# releborne.net
KiCad netlist of a schematic drawn in EAGLE
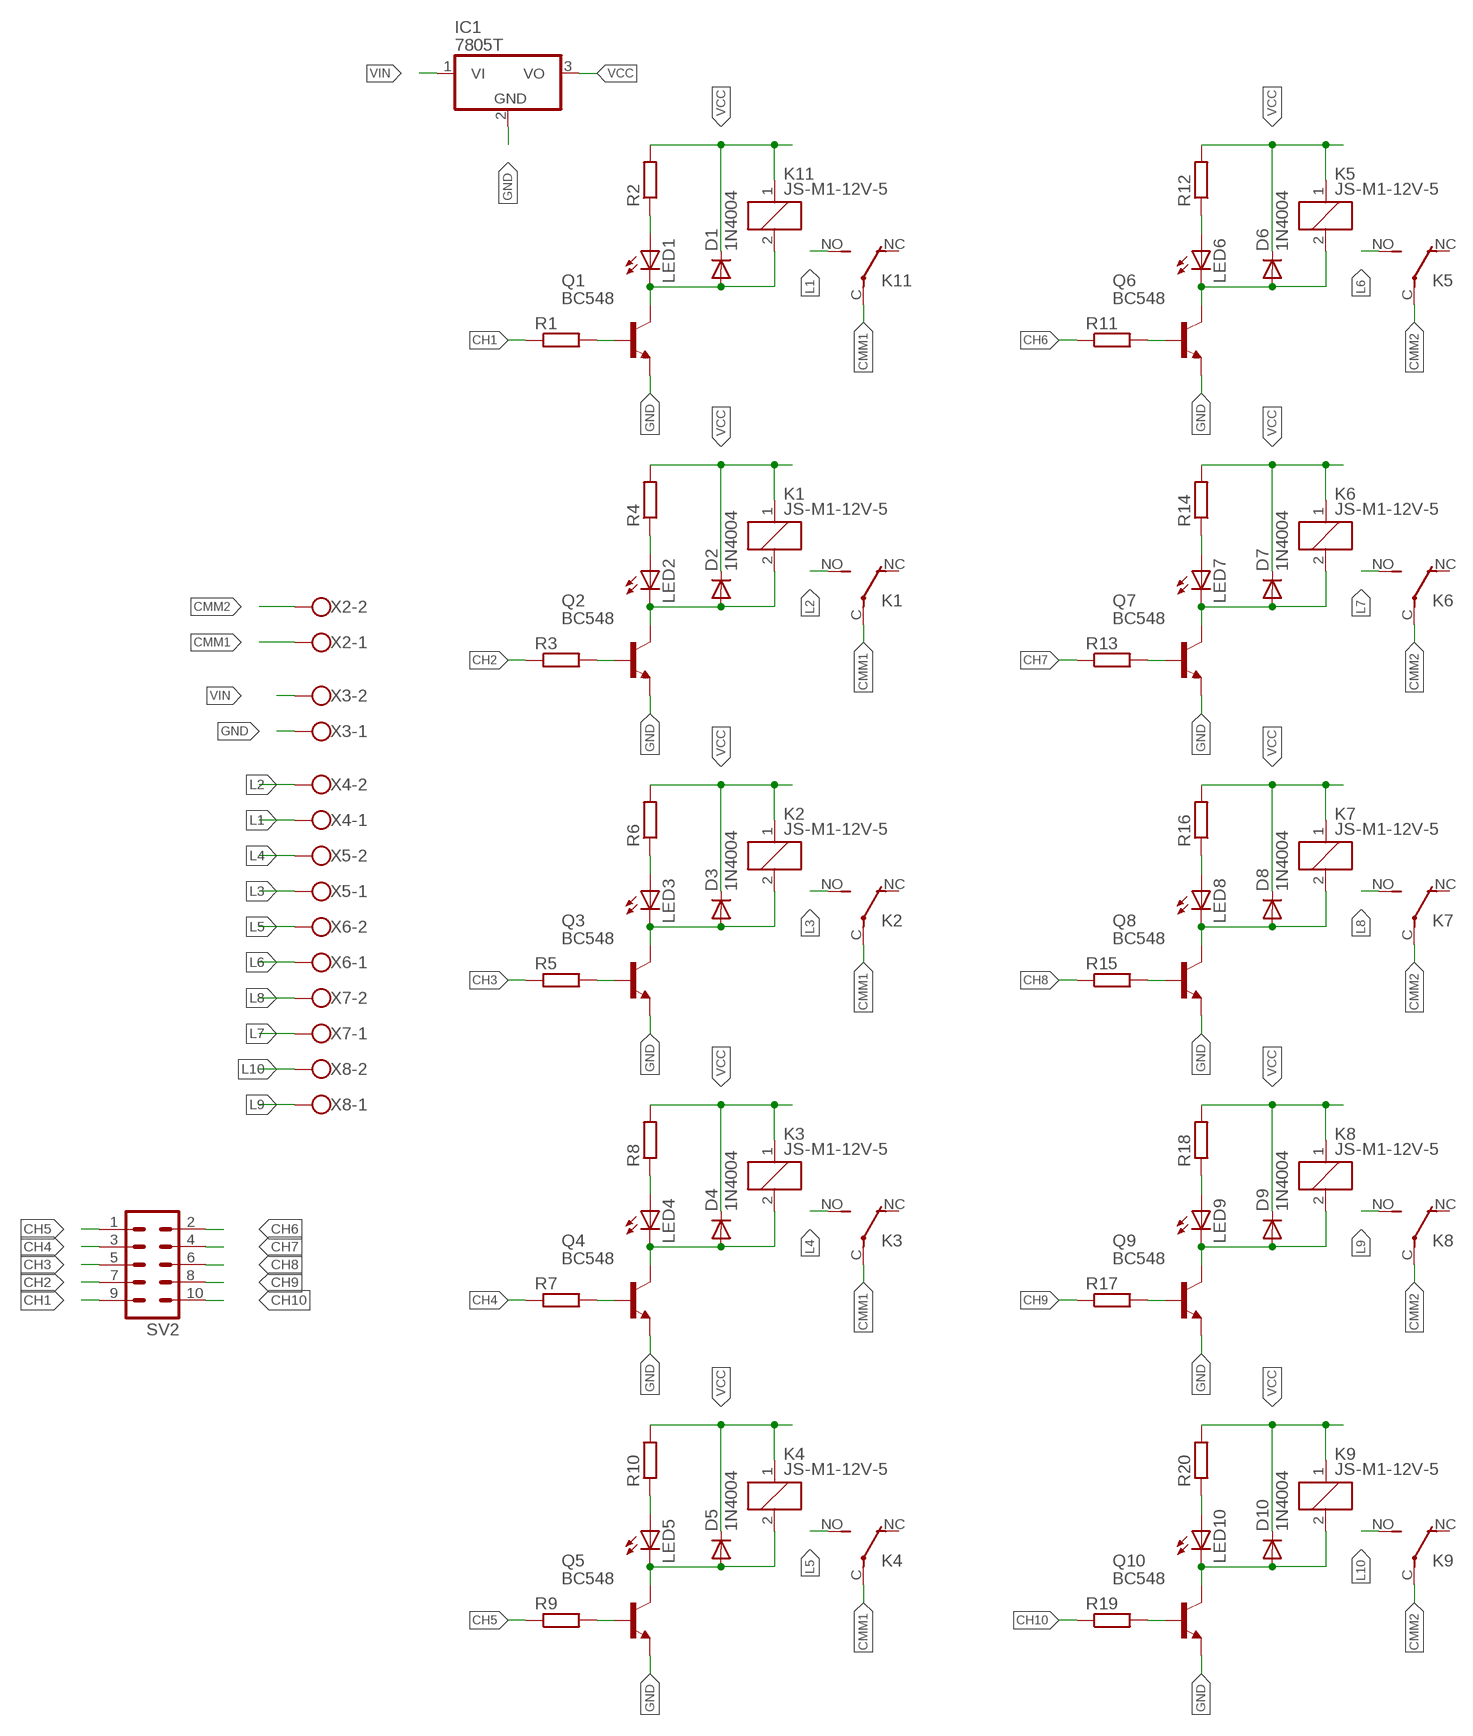
[diagram p0: schematic, sheet 1]

(export (version "E")
  (design (tool "Eeschema 10.0.6"))
  (components
    (comp (ref "D1")
      (value "1N4004")
      (footprint "eagle-import:DO41-10")
      (libsource (lib "eagle-import") (part "1N4004"))
    )
    (comp (ref "D2")
      (value "1N4004")
      (footprint "eagle-import:DO41-10")
      (libsource (lib "eagle-import") (part "1N4004"))
    )
    (comp (ref "D3")
      (value "1N4004")
      (footprint "eagle-import:DO41-10")
      (libsource (lib "eagle-import") (part "1N4004"))
    )
    (comp (ref "D4")
      (value "1N4004")
      (footprint "eagle-import:DO41-10")
      (libsource (lib "eagle-import") (part "1N4004"))
    )
    (comp (ref "D5")
      (value "1N4004")
      (footprint "eagle-import:DO41-10")
      (libsource (lib "eagle-import") (part "1N4004"))
    )
    (comp (ref "D6")
      (value "1N4004")
      (footprint "eagle-import:DO41-10")
      (libsource (lib "eagle-import") (part "1N4004"))
    )
    (comp (ref "D7")
      (value "1N4004")
      (footprint "eagle-import:DO41-10")
      (libsource (lib "eagle-import") (part "1N4004"))
    )
    (comp (ref "D8")
      (value "1N4004")
      (footprint "eagle-import:DO41-10")
      (libsource (lib "eagle-import") (part "1N4004"))
    )
    (comp (ref "D9")
      (value "1N4004")
      (footprint "eagle-import:DO41-10")
      (libsource (lib "eagle-import") (part "1N4004"))
    )
    (comp (ref "D10")
      (value "1N4004")
      (footprint "eagle-import:DO41-10")
      (libsource (lib "eagle-import") (part "1N4004"))
    )
    (comp (ref "IC1")
      (value "7805T")
      (footprint "eagle-import:TO220H")
      (libsource (lib "eagle-import") (part "78T05"))
    )
    (comp (ref "K1")
      (value "JS-M1-12V-5")
      (footprint "eagle-import:JS-M")
      (fields (field (name "MF") "FARNELL") (field (name "MPN") "JSM1-12V-5"))
      (libsource (lib "eagle-import") (part "JS-M1-12V-5"))
    )
    (comp (ref "K2")
      (value "JS-M1-12V-5")
      (footprint "eagle-import:JS-M")
      (fields (field (name "MF") "FARNELL") (field (name "MPN") "JSM1-12V-5"))
      (libsource (lib "eagle-import") (part "JS-M1-12V-5"))
    )
    (comp (ref "K3")
      (value "JS-M1-12V-5")
      (footprint "eagle-import:JS-M")
      (fields (field (name "MF") "FARNELL") (field (name "MPN") "JSM1-12V-5"))
      (libsource (lib "eagle-import") (part "JS-M1-12V-5"))
    )
    (comp (ref "K4")
      (value "JS-M1-12V-5")
      (footprint "eagle-import:JS-M")
      (fields (field (name "MF") "FARNELL") (field (name "MPN") "JSM1-12V-5"))
      (libsource (lib "eagle-import") (part "JS-M1-12V-5"))
    )
    (comp (ref "K5")
      (value "JS-M1-12V-5")
      (footprint "eagle-import:JS-M")
      (fields (field (name "MF") "FARNELL") (field (name "MPN") "JSM1-12V-5"))
      (libsource (lib "eagle-import") (part "JS-M1-12V-5"))
    )
    (comp (ref "K6")
      (value "JS-M1-12V-5")
      (footprint "eagle-import:JS-M")
      (fields (field (name "MF") "FARNELL") (field (name "MPN") "JSM1-12V-5"))
      (libsource (lib "eagle-import") (part "JS-M1-12V-5"))
    )
    (comp (ref "K7")
      (value "JS-M1-12V-5")
      (footprint "eagle-import:JS-M")
      (fields (field (name "MF") "FARNELL") (field (name "MPN") "JSM1-12V-5"))
      (libsource (lib "eagle-import") (part "JS-M1-12V-5"))
    )
    (comp (ref "K8")
      (value "JS-M1-12V-5")
      (footprint "eagle-import:JS-M")
      (fields (field (name "MF") "FARNELL") (field (name "MPN") "JSM1-12V-5"))
      (libsource (lib "eagle-import") (part "JS-M1-12V-5"))
    )
    (comp (ref "K9")
      (value "JS-M1-12V-5")
      (footprint "eagle-import:JS-M")
      (fields (field (name "MF") "FARNELL") (field (name "MPN") "JSM1-12V-5"))
      (libsource (lib "eagle-import") (part "JS-M1-12V-5"))
    )
    (comp (ref "K11")
      (value "JS-M1-12V-5")
      (footprint "eagle-import:JS-M")
      (fields (field (name "MF") "FARNELL") (field (name "MPN") "JSM1-12V-5"))
      (libsource (lib "eagle-import") (part "JS-M1-12V-5"))
    )
    (comp (ref "LED1")
      (value "LED5MM")
      (footprint "eagle-import:LED5MM")
      (libsource (lib "eagle-import") (part "LED5MM"))
    )
    (comp (ref "LED2")
      (value "LED5MM")
      (footprint "eagle-import:LED5MM")
      (libsource (lib "eagle-import") (part "LED5MM"))
    )
    (comp (ref "LED3")
      (value "LED5MM")
      (footprint "eagle-import:LED5MM")
      (libsource (lib "eagle-import") (part "LED5MM"))
    )
    (comp (ref "LED4")
      (value "LED5MM")
      (footprint "eagle-import:LED5MM")
      (libsource (lib "eagle-import") (part "LED5MM"))
    )
    (comp (ref "LED5")
      (value "LED5MM")
      (footprint "eagle-import:LED5MM")
      (libsource (lib "eagle-import") (part "LED5MM"))
    )
    (comp (ref "LED6")
      (value "LED5MM")
      (footprint "eagle-import:LED5MM")
      (libsource (lib "eagle-import") (part "LED5MM"))
    )
    (comp (ref "LED7")
      (value "LED5MM")
      (footprint "eagle-import:LED5MM")
      (libsource (lib "eagle-import") (part "LED5MM"))
    )
    (comp (ref "LED8")
      (value "LED5MM")
      (footprint "eagle-import:LED5MM")
      (libsource (lib "eagle-import") (part "LED5MM"))
    )
    (comp (ref "LED9")
      (value "LED5MM")
      (footprint "eagle-import:LED5MM")
      (libsource (lib "eagle-import") (part "LED5MM"))
    )
    (comp (ref "LED10")
      (value "LED5MM")
      (footprint "eagle-import:LED5MM")
      (libsource (lib "eagle-import") (part "LED5MM"))
    )
    (comp (ref "Q1")
      (value "BC548")
      (footprint "eagle-import:TO92-EBC")
      (libsource (lib "eagle-import") (part "BC548"))
    )
    (comp (ref "Q2")
      (value "BC548")
      (footprint "eagle-import:TO92-EBC")
      (libsource (lib "eagle-import") (part "BC548"))
    )
    (comp (ref "Q3")
      (value "BC548")
      (footprint "eagle-import:TO92-EBC")
      (libsource (lib "eagle-import") (part "BC548"))
    )
    (comp (ref "Q4")
      (value "BC548")
      (footprint "eagle-import:TO92-EBC")
      (libsource (lib "eagle-import") (part "BC548"))
    )
    (comp (ref "Q5")
      (value "BC548")
      (footprint "eagle-import:TO92-EBC")
      (libsource (lib "eagle-import") (part "BC548"))
    )
    (comp (ref "Q6")
      (value "BC548")
      (footprint "eagle-import:TO92-EBC")
      (libsource (lib "eagle-import") (part "BC548"))
    )
    (comp (ref "Q7")
      (value "BC548")
      (footprint "eagle-import:TO92-EBC")
      (libsource (lib "eagle-import") (part "BC548"))
    )
    (comp (ref "Q8")
      (value "BC548")
      (footprint "eagle-import:TO92-EBC")
      (libsource (lib "eagle-import") (part "BC548"))
    )
    (comp (ref "Q9")
      (value "BC548")
      (footprint "eagle-import:TO92-EBC")
      (libsource (lib "eagle-import") (part "BC548"))
    )
    (comp (ref "Q10")
      (value "BC548")
      (footprint "eagle-import:TO92-EBC")
      (libsource (lib "eagle-import") (part "BC548"))
    )
    (comp (ref "R1")
      (value "R-EU_0207/10")
      (footprint "eagle-import:0207_10")
      (libsource (lib "eagle-import") (part "R-EU_0207/10"))
    )
    (comp (ref "R2")
      (value "R-EU_0207/10")
      (footprint "eagle-import:0207_10")
      (libsource (lib "eagle-import") (part "R-EU_0207/10"))
    )
    (comp (ref "R3")
      (value "R-EU_0207/10")
      (footprint "eagle-import:0207_10")
      (libsource (lib "eagle-import") (part "R-EU_0207/10"))
    )
    (comp (ref "R4")
      (value "R-EU_0207/10")
      (footprint "eagle-import:0207_10")
      (libsource (lib "eagle-import") (part "R-EU_0207/10"))
    )
    (comp (ref "R5")
      (value "R-EU_0207/10")
      (footprint "eagle-import:0207_10")
      (libsource (lib "eagle-import") (part "R-EU_0207/10"))
    )
    (comp (ref "R6")
      (value "R-EU_0207/10")
      (footprint "eagle-import:0207_10")
      (libsource (lib "eagle-import") (part "R-EU_0207/10"))
    )
    (comp (ref "R7")
      (value "R-EU_0207/10")
      (footprint "eagle-import:0207_10")
      (libsource (lib "eagle-import") (part "R-EU_0207/10"))
    )
    (comp (ref "R8")
      (value "R-EU_0207/10")
      (footprint "eagle-import:0207_10")
      (libsource (lib "eagle-import") (part "R-EU_0207/10"))
    )
    (comp (ref "R9")
      (value "R-EU_0207/10")
      (footprint "eagle-import:0207_10")
      (libsource (lib "eagle-import") (part "R-EU_0207/10"))
    )
    (comp (ref "R10")
      (value "R-EU_0207/10")
      (footprint "eagle-import:0207_10")
      (libsource (lib "eagle-import") (part "R-EU_0207/10"))
    )
    (comp (ref "R11")
      (value "R-EU_0207/10")
      (footprint "eagle-import:0207_10")
      (libsource (lib "eagle-import") (part "R-EU_0207/10"))
    )
    (comp (ref "R12")
      (value "R-EU_0207/10")
      (footprint "eagle-import:0207_10")
      (libsource (lib "eagle-import") (part "R-EU_0207/10"))
    )
    (comp (ref "R13")
      (value "R-EU_0207/10")
      (footprint "eagle-import:0207_10")
      (libsource (lib "eagle-import") (part "R-EU_0207/10"))
    )
    (comp (ref "R14")
      (value "R-EU_0207/10")
      (footprint "eagle-import:0207_10")
      (libsource (lib "eagle-import") (part "R-EU_0207/10"))
    )
    (comp (ref "R15")
      (value "R-EU_0207/10")
      (footprint "eagle-import:0207_10")
      (libsource (lib "eagle-import") (part "R-EU_0207/10"))
    )
    (comp (ref "R16")
      (value "R-EU_0207/10")
      (footprint "eagle-import:0207_10")
      (libsource (lib "eagle-import") (part "R-EU_0207/10"))
    )
    (comp (ref "R17")
      (value "R-EU_0207/10")
      (footprint "eagle-import:0207_10")
      (libsource (lib "eagle-import") (part "R-EU_0207/10"))
    )
    (comp (ref "R18")
      (value "R-EU_0207/10")
      (footprint "eagle-import:0207_10")
      (libsource (lib "eagle-import") (part "R-EU_0207/10"))
    )
    (comp (ref "R19")
      (value "R-EU_0207/10")
      (footprint "eagle-import:0207_10")
      (libsource (lib "eagle-import") (part "R-EU_0207/10"))
    )
    (comp (ref "R20")
      (value "R-EU_0207/10")
      (footprint "eagle-import:0207_10")
      (libsource (lib "eagle-import") (part "R-EU_0207/10"))
    )
    (comp (ref "SV2")
      (value "MA05-2")
      (footprint "eagle-import:MA05-2")
      (libsource (lib "eagle-import") (part "MA05-2"))
    )
    (comp (ref "X2")
      (value "W237-102")
      (footprint "eagle-import:W237-102")
      (fields (field (name "MPN") "237-102"))
      (libsource (lib "eagle-import") (part "W237-102"))
    )
    (comp (ref "X3")
      (value "W237-102")
      (footprint "eagle-import:W237-102")
      (fields (field (name "MPN") "237-102"))
      (libsource (lib "eagle-import") (part "W237-102"))
    )
    (comp (ref "X4")
      (value "W237-102")
      (footprint "eagle-import:W237-102")
      (fields (field (name "MPN") "237-102"))
      (libsource (lib "eagle-import") (part "W237-102"))
    )
    (comp (ref "X5")
      (value "W237-102")
      (footprint "eagle-import:W237-102")
      (fields (field (name "MPN") "237-102"))
      (libsource (lib "eagle-import") (part "W237-102"))
    )
    (comp (ref "X6")
      (value "W237-102")
      (footprint "eagle-import:W237-102")
      (fields (field (name "MPN") "237-102"))
      (libsource (lib "eagle-import") (part "W237-102"))
    )
    (comp (ref "X7")
      (value "W237-102")
      (footprint "eagle-import:W237-102")
      (fields (field (name "MPN") "237-102"))
      (libsource (lib "eagle-import") (part "W237-102"))
    )
    (comp (ref "X8")
      (value "W237-102")
      (footprint "eagle-import:W237-102")
      (fields (field (name "MPN") "237-102"))
      (libsource (lib "eagle-import") (part "W237-102"))
    )
  )
  (nets
    (net (code "1") (name "CH1") (class "Default")
      (node (ref "R1") (pin "1") (pinfunction "1_1") (pintype "passive"))
      (node (ref "SV2") (pin "9") (pinfunction "9_9") (pintype "passive"))
    )
    (net (code "2") (name "CH2") (class "Default")
      (node (ref "R3") (pin "1") (pinfunction "1_1") (pintype "passive"))
      (node (ref "SV2") (pin "7") (pinfunction "7_7") (pintype "passive"))
    )
    (net (code "3") (name "CH3") (class "Default")
      (node (ref "R5") (pin "1") (pinfunction "1_1") (pintype "passive"))
      (node (ref "SV2") (pin "5") (pinfunction "5_5") (pintype "passive"))
    )
    (net (code "4") (name "CH4") (class "Default")
      (node (ref "R7") (pin "1") (pinfunction "1_1") (pintype "passive"))
      (node (ref "SV2") (pin "3") (pinfunction "3_3") (pintype "passive"))
    )
    (net (code "5") (name "CH5") (class "Default")
      (node (ref "R9") (pin "1") (pinfunction "1_1") (pintype "passive"))
      (node (ref "SV2") (pin "1") (pinfunction "1_1") (pintype "passive"))
    )
    (net (code "6") (name "CH6") (class "Default")
      (node (ref "R11") (pin "1") (pinfunction "1_1") (pintype "passive"))
      (node (ref "SV2") (pin "2") (pinfunction "2_2") (pintype "passive"))
    )
    (net (code "7") (name "CH7") (class "Default")
      (node (ref "R13") (pin "1") (pinfunction "1_1") (pintype "passive"))
      (node (ref "SV2") (pin "4") (pinfunction "4_4") (pintype "passive"))
    )
    (net (code "8") (name "CH8") (class "Default")
      (node (ref "R15") (pin "1") (pinfunction "1_1") (pintype "passive"))
      (node (ref "SV2") (pin "6") (pinfunction "6_6") (pintype "passive"))
    )
    (net (code "9") (name "CH9") (class "Default")
      (node (ref "R17") (pin "1") (pinfunction "1_1") (pintype "passive"))
      (node (ref "SV2") (pin "8") (pinfunction "8_8") (pintype "passive"))
    )
    (net (code "10") (name "CH10") (class "Default")
      (node (ref "R19") (pin "1") (pinfunction "1_1") (pintype "passive"))
      (node (ref "SV2") (pin "10") (pinfunction "10_10") (pintype "passive"))
    )
    (net (code "11") (name "CMM1") (class "Default")
      (node (ref "K1") (pin "C") (pinfunction "P_C") (pintype "passive"))
      (node (ref "K11") (pin "C") (pinfunction "P_C") (pintype "passive"))
      (node (ref "K2") (pin "C") (pinfunction "P_C") (pintype "passive"))
      (node (ref "K3") (pin "C") (pinfunction "P_C") (pintype "passive"))
      (node (ref "K4") (pin "C") (pinfunction "P_C") (pintype "passive"))
      (node (ref "X2") (pin "1") (pinfunction "KL_1") (pintype "passive"))
    )
    (net (code "12") (name "CMM2") (class "Default")
      (node (ref "K5") (pin "C") (pinfunction "P_C") (pintype "passive"))
      (node (ref "K6") (pin "C") (pinfunction "P_C") (pintype "passive"))
      (node (ref "K7") (pin "C") (pinfunction "P_C") (pintype "passive"))
      (node (ref "K8") (pin "C") (pinfunction "P_C") (pintype "passive"))
      (node (ref "K9") (pin "C") (pinfunction "P_C") (pintype "passive"))
      (node (ref "X2") (pin "2") (pinfunction "KL_2") (pintype "passive"))
    )
    (net (code "13") (name "GND") (class "Default")
      (node (ref "IC1") (pin "2") (pinfunction "GND_2") (pintype "passive"))
      (node (ref "Q1") (pin "E") (pinfunction "E_E") (pintype "passive"))
      (node (ref "Q10") (pin "E") (pinfunction "E_E") (pintype "passive"))
      (node (ref "Q2") (pin "E") (pinfunction "E_E") (pintype "passive"))
      (node (ref "Q3") (pin "E") (pinfunction "E_E") (pintype "passive"))
      (node (ref "Q4") (pin "E") (pinfunction "E_E") (pintype "passive"))
      (node (ref "Q5") (pin "E") (pinfunction "E_E") (pintype "passive"))
      (node (ref "Q6") (pin "E") (pinfunction "E_E") (pintype "passive"))
      (node (ref "Q7") (pin "E") (pinfunction "E_E") (pintype "passive"))
      (node (ref "Q8") (pin "E") (pinfunction "E_E") (pintype "passive"))
      (node (ref "Q9") (pin "E") (pinfunction "E_E") (pintype "passive"))
      (node (ref "X3") (pin "1") (pinfunction "KL_1") (pintype "passive"))
    )
    (net (code "14") (name "L1") (class "Default")
      (node (ref "K11") (pin "NO") (pinfunction "S_NO") (pintype "passive"))
      (node (ref "X4") (pin "1") (pinfunction "KL_1") (pintype "passive"))
    )
    (net (code "15") (name "L2") (class "Default")
      (node (ref "K1") (pin "NO") (pinfunction "S_NO") (pintype "passive"))
      (node (ref "X4") (pin "2") (pinfunction "KL_2") (pintype "passive"))
    )
    (net (code "16") (name "L3") (class "Default")
      (node (ref "K2") (pin "NO") (pinfunction "S_NO") (pintype "passive"))
      (node (ref "X5") (pin "1") (pinfunction "KL_1") (pintype "passive"))
    )
    (net (code "17") (name "L4") (class "Default")
      (node (ref "K3") (pin "NO") (pinfunction "S_NO") (pintype "passive"))
      (node (ref "X5") (pin "2") (pinfunction "KL_2") (pintype "passive"))
    )
    (net (code "18") (name "L5") (class "Default")
      (node (ref "K4") (pin "NO") (pinfunction "S_NO") (pintype "passive"))
      (node (ref "X6") (pin "2") (pinfunction "KL_2") (pintype "passive"))
    )
    (net (code "19") (name "L6") (class "Default")
      (node (ref "K5") (pin "NO") (pinfunction "S_NO") (pintype "passive"))
      (node (ref "X6") (pin "1") (pinfunction "KL_1") (pintype "passive"))
    )
    (net (code "20") (name "L7") (class "Default")
      (node (ref "K6") (pin "NO") (pinfunction "S_NO") (pintype "passive"))
      (node (ref "X7") (pin "1") (pinfunction "KL_1") (pintype "passive"))
    )
    (net (code "21") (name "L8") (class "Default")
      (node (ref "K7") (pin "NO") (pinfunction "S_NO") (pintype "passive"))
      (node (ref "X7") (pin "2") (pinfunction "KL_2") (pintype "passive"))
    )
    (net (code "22") (name "L9") (class "Default")
      (node (ref "K8") (pin "NO") (pinfunction "S_NO") (pintype "passive"))
      (node (ref "X8") (pin "1") (pinfunction "KL_1") (pintype "passive"))
    )
    (net (code "23") (name "L10") (class "Default")
      (node (ref "K9") (pin "NO") (pinfunction "S_NO") (pintype "passive"))
      (node (ref "X8") (pin "2") (pinfunction "KL_2") (pintype "passive"))
    )
    (net (code "24") (name "Net-(LED1-C)") (class "Default")
      (node (ref "D1") (pin "A") (pinfunction "A_A") (pintype "passive"))
      (node (ref "K11") (pin "2") (pinfunction "2_2") (pintype "passive"))
      (node (ref "LED1") (pin "K") (pinfunction "C_K") (pintype "passive"))
      (node (ref "Q1") (pin "C") (pinfunction "C_C") (pintype "passive"))
    )
    (net (code "25") (name "Net-(LED1-PadA)") (class "Default")
      (node (ref "LED1") (pin "A") (pinfunction "A_A") (pintype "passive"))
      (node (ref "R2") (pin "1") (pinfunction "1_1") (pintype "passive"))
    )
    (net (code "26") (name "Net-(LED2-C)") (class "Default")
      (node (ref "D2") (pin "A") (pinfunction "A_A") (pintype "passive"))
      (node (ref "K1") (pin "2") (pinfunction "2_2") (pintype "passive"))
      (node (ref "LED2") (pin "K") (pinfunction "C_K") (pintype "passive"))
      (node (ref "Q2") (pin "C") (pinfunction "C_C") (pintype "passive"))
    )
    (net (code "27") (name "Net-(LED2-PadA)") (class "Default")
      (node (ref "LED2") (pin "A") (pinfunction "A_A") (pintype "passive"))
      (node (ref "R4") (pin "1") (pinfunction "1_1") (pintype "passive"))
    )
    (net (code "28") (name "Net-(LED3-C)") (class "Default")
      (node (ref "D3") (pin "A") (pinfunction "A_A") (pintype "passive"))
      (node (ref "K2") (pin "2") (pinfunction "2_2") (pintype "passive"))
      (node (ref "LED3") (pin "K") (pinfunction "C_K") (pintype "passive"))
      (node (ref "Q3") (pin "C") (pinfunction "C_C") (pintype "passive"))
    )
    (net (code "29") (name "Net-(LED3-PadA)") (class "Default")
      (node (ref "LED3") (pin "A") (pinfunction "A_A") (pintype "passive"))
      (node (ref "R6") (pin "1") (pinfunction "1_1") (pintype "passive"))
    )
    (net (code "30") (name "Net-(LED4-C)") (class "Default")
      (node (ref "D4") (pin "A") (pinfunction "A_A") (pintype "passive"))
      (node (ref "K3") (pin "2") (pinfunction "2_2") (pintype "passive"))
      (node (ref "LED4") (pin "K") (pinfunction "C_K") (pintype "passive"))
      (node (ref "Q4") (pin "C") (pinfunction "C_C") (pintype "passive"))
    )
    (net (code "31") (name "Net-(LED4-PadA)") (class "Default")
      (node (ref "LED4") (pin "A") (pinfunction "A_A") (pintype "passive"))
      (node (ref "R8") (pin "1") (pinfunction "1_1") (pintype "passive"))
    )
    (net (code "32") (name "Net-(LED5-C)") (class "Default")
      (node (ref "D5") (pin "A") (pinfunction "A_A") (pintype "passive"))
      (node (ref "K4") (pin "2") (pinfunction "2_2") (pintype "passive"))
      (node (ref "LED5") (pin "K") (pinfunction "C_K") (pintype "passive"))
      (node (ref "Q5") (pin "C") (pinfunction "C_C") (pintype "passive"))
    )
    (net (code "33") (name "Net-(LED5-PadA)") (class "Default")
      (node (ref "LED5") (pin "A") (pinfunction "A_A") (pintype "passive"))
      (node (ref "R10") (pin "1") (pinfunction "1_1") (pintype "passive"))
    )
    (net (code "34") (name "Net-(LED6-C)") (class "Default")
      (node (ref "D6") (pin "A") (pinfunction "A_A") (pintype "passive"))
      (node (ref "K5") (pin "2") (pinfunction "2_2") (pintype "passive"))
      (node (ref "LED6") (pin "K") (pinfunction "C_K") (pintype "passive"))
      (node (ref "Q6") (pin "C") (pinfunction "C_C") (pintype "passive"))
    )
    (net (code "35") (name "Net-(LED6-PadA)") (class "Default")
      (node (ref "LED6") (pin "A") (pinfunction "A_A") (pintype "passive"))
      (node (ref "R12") (pin "1") (pinfunction "1_1") (pintype "passive"))
    )
    (net (code "36") (name "Net-(LED7-C)") (class "Default")
      (node (ref "D7") (pin "A") (pinfunction "A_A") (pintype "passive"))
      (node (ref "K6") (pin "2") (pinfunction "2_2") (pintype "passive"))
      (node (ref "LED7") (pin "K") (pinfunction "C_K") (pintype "passive"))
      (node (ref "Q7") (pin "C") (pinfunction "C_C") (pintype "passive"))
    )
    (net (code "37") (name "Net-(LED7-PadA)") (class "Default")
      (node (ref "LED7") (pin "A") (pinfunction "A_A") (pintype "passive"))
      (node (ref "R14") (pin "1") (pinfunction "1_1") (pintype "passive"))
    )
    (net (code "38") (name "Net-(LED8-C)") (class "Default")
      (node (ref "D8") (pin "A") (pinfunction "A_A") (pintype "passive"))
      (node (ref "K7") (pin "2") (pinfunction "2_2") (pintype "passive"))
      (node (ref "LED8") (pin "K") (pinfunction "C_K") (pintype "passive"))
      (node (ref "Q8") (pin "C") (pinfunction "C_C") (pintype "passive"))
    )
    (net (code "39") (name "Net-(LED8-PadA)") (class "Default")
      (node (ref "LED8") (pin "A") (pinfunction "A_A") (pintype "passive"))
      (node (ref "R16") (pin "1") (pinfunction "1_1") (pintype "passive"))
    )
    (net (code "40") (name "Net-(LED9-C)") (class "Default")
      (node (ref "D9") (pin "A") (pinfunction "A_A") (pintype "passive"))
      (node (ref "K8") (pin "2") (pinfunction "2_2") (pintype "passive"))
      (node (ref "LED9") (pin "K") (pinfunction "C_K") (pintype "passive"))
      (node (ref "Q9") (pin "C") (pinfunction "C_C") (pintype "passive"))
    )
    (net (code "41") (name "Net-(LED9-PadA)") (class "Default")
      (node (ref "LED9") (pin "A") (pinfunction "A_A") (pintype "passive"))
      (node (ref "R18") (pin "1") (pinfunction "1_1") (pintype "passive"))
    )
    (net (code "42") (name "Net-(LED10-C)") (class "Default")
      (node (ref "D10") (pin "A") (pinfunction "A_A") (pintype "passive"))
      (node (ref "K9") (pin "2") (pinfunction "2_2") (pintype "passive"))
      (node (ref "LED10") (pin "K") (pinfunction "C_K") (pintype "passive"))
      (node (ref "Q10") (pin "C") (pinfunction "C_C") (pintype "passive"))
    )
    (net (code "43") (name "Net-(LED10-PadA)") (class "Default")
      (node (ref "LED10") (pin "A") (pinfunction "A_A") (pintype "passive"))
      (node (ref "R20") (pin "1") (pinfunction "1_1") (pintype "passive"))
    )
    (net (code "44") (name "Net-(Q1-PadB)") (class "Default")
      (node (ref "Q1") (pin "B") (pinfunction "B_B") (pintype "passive"))
      (node (ref "R1") (pin "2") (pinfunction "2_2") (pintype "passive"))
    )
    (net (code "45") (name "Net-(Q2-PadB)") (class "Default")
      (node (ref "Q2") (pin "B") (pinfunction "B_B") (pintype "passive"))
      (node (ref "R3") (pin "2") (pinfunction "2_2") (pintype "passive"))
    )
    (net (code "46") (name "Net-(Q3-PadB)") (class "Default")
      (node (ref "Q3") (pin "B") (pinfunction "B_B") (pintype "passive"))
      (node (ref "R5") (pin "2") (pinfunction "2_2") (pintype "passive"))
    )
    (net (code "47") (name "Net-(Q4-PadB)") (class "Default")
      (node (ref "Q4") (pin "B") (pinfunction "B_B") (pintype "passive"))
      (node (ref "R7") (pin "2") (pinfunction "2_2") (pintype "passive"))
    )
    (net (code "48") (name "Net-(Q5-PadB)") (class "Default")
      (node (ref "Q5") (pin "B") (pinfunction "B_B") (pintype "passive"))
      (node (ref "R9") (pin "2") (pinfunction "2_2") (pintype "passive"))
    )
    (net (code "49") (name "Net-(Q6-PadB)") (class "Default")
      (node (ref "Q6") (pin "B") (pinfunction "B_B") (pintype "passive"))
      (node (ref "R11") (pin "2") (pinfunction "2_2") (pintype "passive"))
    )
    (net (code "50") (name "Net-(Q7-PadB)") (class "Default")
      (node (ref "Q7") (pin "B") (pinfunction "B_B") (pintype "passive"))
      (node (ref "R13") (pin "2") (pinfunction "2_2") (pintype "passive"))
    )
    (net (code "51") (name "Net-(Q8-PadB)") (class "Default")
      (node (ref "Q8") (pin "B") (pinfunction "B_B") (pintype "passive"))
      (node (ref "R15") (pin "2") (pinfunction "2_2") (pintype "passive"))
    )
    (net (code "52") (name "Net-(Q9-PadB)") (class "Default")
      (node (ref "Q9") (pin "B") (pinfunction "B_B") (pintype "passive"))
      (node (ref "R17") (pin "2") (pinfunction "2_2") (pintype "passive"))
    )
    (net (code "53") (name "Net-(Q10-PadB)") (class "Default")
      (node (ref "Q10") (pin "B") (pinfunction "B_B") (pintype "passive"))
      (node (ref "R19") (pin "2") (pinfunction "2_2") (pintype "passive"))
    )
    (net (code "54") (name "VCC") (class "Default")
      (node (ref "D1") (pin "C") (pinfunction "C_C") (pintype "passive"))
      (node (ref "D10") (pin "C") (pinfunction "C_C") (pintype "passive"))
      (node (ref "D2") (pin "C") (pinfunction "C_C") (pintype "passive"))
      (node (ref "D3") (pin "C") (pinfunction "C_C") (pintype "passive"))
      (node (ref "D4") (pin "C") (pinfunction "C_C") (pintype "passive"))
      (node (ref "D5") (pin "C") (pinfunction "C_C") (pintype "passive"))
      (node (ref "D6") (pin "C") (pinfunction "C_C") (pintype "passive"))
      (node (ref "D7") (pin "C") (pinfunction "C_C") (pintype "passive"))
      (node (ref "D8") (pin "C") (pinfunction "C_C") (pintype "passive"))
      (node (ref "D9") (pin "C") (pinfunction "C_C") (pintype "passive"))
      (node (ref "IC1") (pin "3") (pinfunction "VO_3") (pintype "passive"))
      (node (ref "K1") (pin "1") (pinfunction "1_1") (pintype "passive"))
      (node (ref "K11") (pin "1") (pinfunction "1_1") (pintype "passive"))
      (node (ref "K2") (pin "1") (pinfunction "1_1") (pintype "passive"))
      (node (ref "K3") (pin "1") (pinfunction "1_1") (pintype "passive"))
      (node (ref "K4") (pin "1") (pinfunction "1_1") (pintype "passive"))
      (node (ref "K5") (pin "1") (pinfunction "1_1") (pintype "passive"))
      (node (ref "K6") (pin "1") (pinfunction "1_1") (pintype "passive"))
      (node (ref "K7") (pin "1") (pinfunction "1_1") (pintype "passive"))
      (node (ref "K8") (pin "1") (pinfunction "1_1") (pintype "passive"))
      (node (ref "K9") (pin "1") (pinfunction "1_1") (pintype "passive"))
      (node (ref "R10") (pin "2") (pinfunction "2_2") (pintype "passive"))
      (node (ref "R12") (pin "2") (pinfunction "2_2") (pintype "passive"))
      (node (ref "R14") (pin "2") (pinfunction "2_2") (pintype "passive"))
      (node (ref "R16") (pin "2") (pinfunction "2_2") (pintype "passive"))
      (node (ref "R18") (pin "2") (pinfunction "2_2") (pintype "passive"))
      (node (ref "R2") (pin "2") (pinfunction "2_2") (pintype "passive"))
      (node (ref "R20") (pin "2") (pinfunction "2_2") (pintype "passive"))
      (node (ref "R4") (pin "2") (pinfunction "2_2") (pintype "passive"))
      (node (ref "R6") (pin "2") (pinfunction "2_2") (pintype "passive"))
      (node (ref "R8") (pin "2") (pinfunction "2_2") (pintype "passive"))
    )
    (net (code "55") (name "VIN") (class "Default")
      (node (ref "IC1") (pin "1") (pinfunction "VI_1") (pintype "input"))
      (node (ref "X3") (pin "2") (pinfunction "KL_2") (pintype "passive"))
    )
    (net (code "56") (name "unconnected-(K1B-O-PadNC)") (class "Default")
      (node (ref "K1") (pin "NC") (pinfunction "O_NC") (pintype "passive"))
    )
    (net (code "57") (name "unconnected-(K2B-O-PadNC)") (class "Default")
      (node (ref "K2") (pin "NC") (pinfunction "O_NC") (pintype "passive"))
    )
    (net (code "58") (name "unconnected-(K3B-O-PadNC)") (class "Default")
      (node (ref "K3") (pin "NC") (pinfunction "O_NC") (pintype "passive"))
    )
    (net (code "59") (name "unconnected-(K4B-O-PadNC)") (class "Default")
      (node (ref "K4") (pin "NC") (pinfunction "O_NC") (pintype "passive"))
    )
    (net (code "60") (name "unconnected-(K5B-O-PadNC)") (class "Default")
      (node (ref "K5") (pin "NC") (pinfunction "O_NC") (pintype "passive"))
    )
    (net (code "61") (name "unconnected-(K6B-O-PadNC)") (class "Default")
      (node (ref "K6") (pin "NC") (pinfunction "O_NC") (pintype "passive"))
    )
    (net (code "62") (name "unconnected-(K7B-O-PadNC)") (class "Default")
      (node (ref "K7") (pin "NC") (pinfunction "O_NC") (pintype "passive"))
    )
    (net (code "63") (name "unconnected-(K8B-O-PadNC)") (class "Default")
      (node (ref "K8") (pin "NC") (pinfunction "O_NC") (pintype "passive"))
    )
    (net (code "64") (name "unconnected-(K9B-O-PadNC)") (class "Default")
      (node (ref "K9") (pin "NC") (pinfunction "O_NC") (pintype "passive"))
    )
    (net (code "65") (name "unconnected-(K11B-O-PadNC)") (class "Default")
      (node (ref "K11") (pin "NC") (pinfunction "O_NC") (pintype "passive"))
    )
  )
)
